# I2C_Multiplexer.net
KiCad netlist of a schematic drawn in Altium Designer
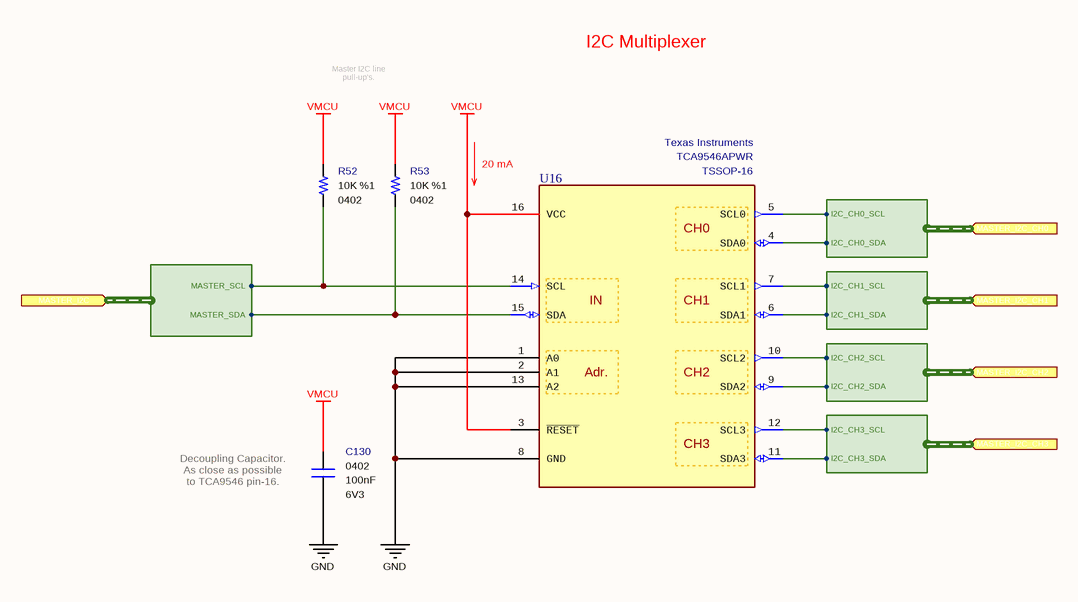
[diagram p0: I2C Multiplexer.SchDoc]

(export (version "E")
  (design (tool "Eeschema 10.0.6"))
  (components
    (comp (ref "C130")
      (value "100nF")
      (footprint "CAPACITOR_0402")
      (description "Capacitor - 100nF [0402-6V3] (Ceramic)")
      (fields
        (field (name "TOLERANCE") "%10")
        (field (name "CASE") "0402")
        (field (name "VOLTAGE") "6V3")
        (field (name "MANUFACTURER PART NUMBER") "04026D104KAT4A")
      )
      (libsource (lib "Ovoo_Library") (part "Capacitor - 100nF [0402-6V3]"))
    )
    (comp (ref "R52")
      (value "10K")
      (footprint "RESISTOR_0402")
      (description "Thick Film Resistors - SMD 1/16 W 10 Kohms 1%")
      (fields
        (field (name "TOLERANCE") "%1")
        (field (name "CASE") "0402")
        (field (name "MANUFACTURER PART NUMBER") "CRCW040210K0FKED")
        (field (name "MOUSER PART NUMBER") "71-CRCW0402-10K-E3")
      )
      (libsource (lib "Ovoo_Library") (part "Resistor - 10K"))
    )
    (comp (ref "R53")
      (value "10K")
      (footprint "RESISTOR_0402")
      (description "Thick Film Resistors - SMD 1/16 W 10 Kohms 1%")
      (fields
        (field (name "TOLERANCE") "%1")
        (field (name "CASE") "0402")
        (field (name "MANUFACTURER PART NUMBER") "CRCW040210K0FKED")
        (field (name "MOUSER PART NUMBER") "71-CRCW0402-10K-E3")
      )
      (libsource (lib "Ovoo_Library") (part "Resistor - 10K"))
    )
    (comp (ref "U16")
      (value "I2C Switch IC")
      (footprint "TSSOP-16")
      (description "Switch ICs - Various 4-Channel I2C and SMBus")
      (fields
        (field (name "MOUSER PART NUMBER") "595-TCA9546APWR")
        (field (name "CASE") "TSSOP-16")
        (field (name "MANUFACTURER PART NUMBER") "TCA9546APWR")
        (field (name "MANUFACTURER NAME") "Texas Instruments")
      )
      (libsource (lib "Ovoo_Library") (part "IC - TCA9546APWR"))
    )
  )
  (nets
    (net (code "6") (name "/I2C_CH0_SCL") (class "Default")
      (node (ref "U16") (pin "5") (pinfunction "SCL0_5") (pintype "output"))
    )
    (net (code "7") (name "/I2C_CH0_SDA") (class "Default")
      (node (ref "U16") (pin "4") (pinfunction "SDA0_4") (pintype "bidirectional"))
    )
    (net (code "8") (name "/I2C_CH1_SCL") (class "Default")
      (node (ref "U16") (pin "7") (pinfunction "SCL1_7") (pintype "output"))
    )
    (net (code "9") (name "/I2C_CH1_SDA") (class "Default")
      (node (ref "U16") (pin "6") (pinfunction "SDA1_6") (pintype "bidirectional"))
    )
    (net (code "10") (name "/I2C_CH2_SCL") (class "Default")
      (node (ref "U16") (pin "10") (pinfunction "SCL2_10") (pintype "output"))
    )
    (net (code "11") (name "/I2C_CH2_SDA") (class "Default")
      (node (ref "U16") (pin "9") (pinfunction "SDA2_9") (pintype "bidirectional"))
    )
    (net (code "12") (name "/I2C_CH3_SCL") (class "Default")
      (node (ref "U16") (pin "12") (pinfunction "SCL3_12") (pintype "output"))
    )
    (net (code "13") (name "/I2C_CH3_SDA") (class "Default")
      (node (ref "U16") (pin "11") (pinfunction "SDA3_11") (pintype "bidirectional"))
    )
    (net (code "14") (name "/MASTER_SCL") (class "Default")
      (node (ref "R52") (pin "1") (pinfunction "1_1") (pintype "passive"))
      (node (ref "U16") (pin "14") (pinfunction "SCL_14") (pintype "input"))
    )
    (net (code "15") (name "/MASTER_SDA") (class "Default")
      (node (ref "R53") (pin "1") (pinfunction "1_1") (pintype "passive"))
      (node (ref "U16") (pin "15") (pinfunction "SDA_15") (pintype "bidirectional"))
    )
    (net (code "21") (name "GND") (class "Default")
      (node (ref "C130") (pin "1") (pinfunction "1_1") (pintype "passive"))
      (node (ref "U16") (pin "1") (pinfunction "A0_1") (pintype "passive"))
      (node (ref "U16") (pin "13") (pinfunction "A2_13") (pintype "passive"))
      (node (ref "U16") (pin "2") (pinfunction "A1_2") (pintype "passive"))
      (node (ref "U16") (pin "8") (pinfunction "GND_8") (pintype "power_in"))
    )
    (net (code "22") (name "VMCU") (class "Default")
      (node (ref "C130") (pin "2") (pinfunction "2_2") (pintype "passive"))
      (node (ref "R52") (pin "2") (pinfunction "2_2") (pintype "passive"))
      (node (ref "R53") (pin "2") (pinfunction "2_2") (pintype "passive"))
      (node (ref "U16") (pin "16") (pinfunction "VCC_16") (pintype "power_in"))
      (node (ref "U16") (pin "3") (pinfunction "~{RESET}_3") (pintype "power_in"))
    )
  )
)
